# ADP7157-1V8.net
KiCad netlist of a schematic drawn in Altium Designer
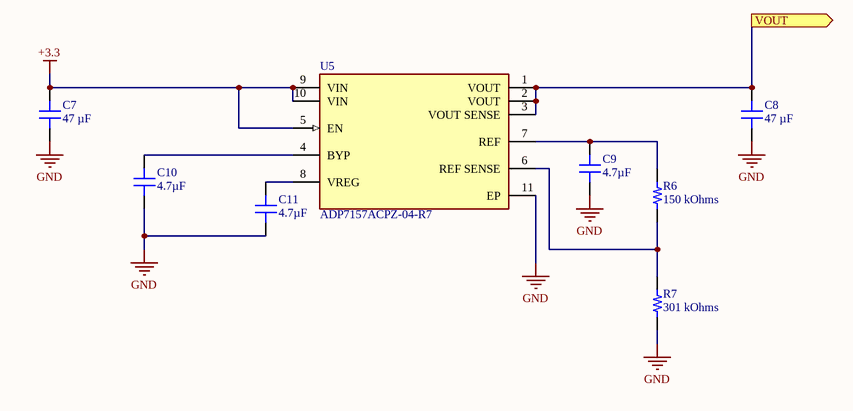
[diagram p0: ADP7157-1V8.SchDoc]

(export (version "E")
  (design (tool "Eeschema 10.0.6"))
  (components
    (comp (ref "C7")
      (value "47 µF")
      (footprint "CAP 0603_1608")
      (description "CAP CER 47UF 6.3V X5R 0603")
      (fields
        (field (name "PART NUMBER") "GRM188R60J476ME01D")
        (field (name "MANUFACTURER") "Murata Electronics")
      )
      (libsource (lib "Celestial Altium Library - altium_library") (part "Capacitor"))
    )
    (comp (ref "C8")
      (value "47 µF")
      (footprint "CAP 0603_1608")
      (description "CAP CER 47UF 6.3V X5R 0603")
      (fields
        (field (name "PART NUMBER") "GRM188R60J476ME01D")
        (field (name "MANUFACTURER") "Murata Electronics")
      )
      (libsource (lib "Celestial Altium Library - altium_library") (part "Capacitor"))
    )
    (comp (ref "C9")
      (value "4.7µF")
      (footprint "CAP 0402_1005")
      (description "CAP CER 4.7UF 10V X5R 0402")
      (fields
        (field (name "PART NUMBER") "GRM155R61A475MEAAD")
        (field (name "MANUFACTURER") "Murata Electronics")
      )
      (libsource (lib "Celestial Altium Library - altium_library") (part "Capacitor"))
    )
    (comp (ref "C10")
      (value "4.7µF")
      (footprint "CAP 0402_1005")
      (description "CAP CER 4.7UF 10V X5R 0402")
      (fields
        (field (name "PART NUMBER") "GRM155R61A475MEAAD")
        (field (name "MANUFACTURER") "Murata Electronics")
      )
      (libsource (lib "Celestial Altium Library - altium_library") (part "Capacitor"))
    )
    (comp (ref "C11")
      (value "4.7µF")
      (footprint "CAP 0402_1005")
      (description "CAP CER 4.7UF 10V X5R 0402")
      (fields
        (field (name "PART NUMBER") "GRM155R61A475MEAAD")
        (field (name "MANUFACTURER") "Murata Electronics")
      )
      (libsource (lib "Celestial Altium Library - altium_library") (part "Capacitor"))
    )
    (comp (ref "R6")
      (value "150 kOhms")
      (footprint "RES 0201_0603")
      (description "RES SMD 150K OHM 5% 1/20W 0201")
      (fields
        (field (name "PART NUMBER") "ERJ-1GNJ154C")
        (field (name "MANUFACTURER") "Panasonic Electronic Components")
      )
      (libsource (lib "Celestial Altium Library - altium_library") (part "Resistor"))
    )
    (comp (ref "R7")
      (value "301 kOhms")
      (footprint "RES 0201_0603")
      (description "RES SMD 301K OHM 1% 1/20W 0201")
      (fields
        (field (name "PART NUMBER") "ERJ-1GNF3013C")
        (field (name "MANUFACTURER") "Panasonic Electronic Components")
      )
      (libsource (lib "Celestial Altium Library - altium_library") (part "Resistor"))
    )
    (comp (ref "U5")
      (value "ADP7157ACPZ-04-R7")
      (footprint "FP-CP-10-9-IPC_B")
      (description "LDO Regulator Pos 1.2V to 3.3V 1.2A 10-Pin LFCSP EP T/R")
      (libsource (lib "SimulaVR") (part "c7b0ea321eafad26d909bd2019a0797"))
    )
  )
  (nets
    (net (code "1") (name "+3.3") (class "Default")
      (node (ref "C7") (pin "2") (pinfunction "2_2") (pintype "passive"))
      (node (ref "U5") (pin "10") (pinfunction "VIN_10") (pintype "power_in"))
      (node (ref "U5") (pin "5") (pinfunction "EN_5") (pintype "input"))
      (node (ref "U5") (pin "9") (pinfunction "VIN_9") (pintype "power_in"))
    )
    (net (code "2") (name "/VOUT") (class "Default")
      (node (ref "C8") (pin "2") (pinfunction "2_2") (pintype "passive"))
      (node (ref "U5") (pin "1") (pinfunction "VOUT_1") (pintype "power_in"))
      (node (ref "U5") (pin "2") (pinfunction "VOUT_2") (pintype "power_in"))
      (node (ref "U5") (pin "3") (pinfunction "VOUT_SENSE_3") (pintype "power_in"))
    )
    (net (code "3") (name "GND") (class "Default")
      (node (ref "C10") (pin "1") (pinfunction "1_1") (pintype "passive"))
      (node (ref "C11") (pin "1") (pinfunction "1_1") (pintype "passive"))
      (node (ref "C7") (pin "1") (pinfunction "1_1") (pintype "passive"))
      (node (ref "C8") (pin "1") (pinfunction "1_1") (pintype "passive"))
      (node (ref "C9") (pin "1") (pinfunction "1_1") (pintype "passive"))
      (node (ref "R7") (pin "1") (pinfunction "1_1") (pintype "passive"))
      (node (ref "U5") (pin "11") (pinfunction "EP_11") (pintype "power_in"))
    )
    (net (code "4") (name "Net-(U5-BYP)") (class "Default")
      (node (ref "C10") (pin "2") (pinfunction "2_2") (pintype "passive"))
      (node (ref "U5") (pin "4") (pinfunction "BYP_4") (pintype "passive"))
    )
    (net (code "5") (name "Net-(U5-REF)") (class "Default")
      (node (ref "C9") (pin "2") (pinfunction "2_2") (pintype "passive"))
      (node (ref "R6") (pin "2") (pinfunction "2_2") (pintype "passive"))
      (node (ref "U5") (pin "7") (pinfunction "REF_7") (pintype "power_in"))
    )
    (net (code "6") (name "Net-(U5-REF_SENSE)") (class "Default")
      (node (ref "R6") (pin "1") (pinfunction "1_1") (pintype "passive"))
      (node (ref "R7") (pin "2") (pinfunction "2_2") (pintype "passive"))
      (node (ref "U5") (pin "6") (pinfunction "REF_SENSE_6") (pintype "power_in"))
    )
    (net (code "7") (name "Net-(U5-VREG)") (class "Default")
      (node (ref "C11") (pin "2") (pinfunction "2_2") (pintype "passive"))
      (node (ref "U5") (pin "8") (pinfunction "VREG_8") (pintype "power_in"))
    )
  )
)
